# Current_Shunt_Amplifier.net
KiCad netlist of a schematic drawn in Altium Designer
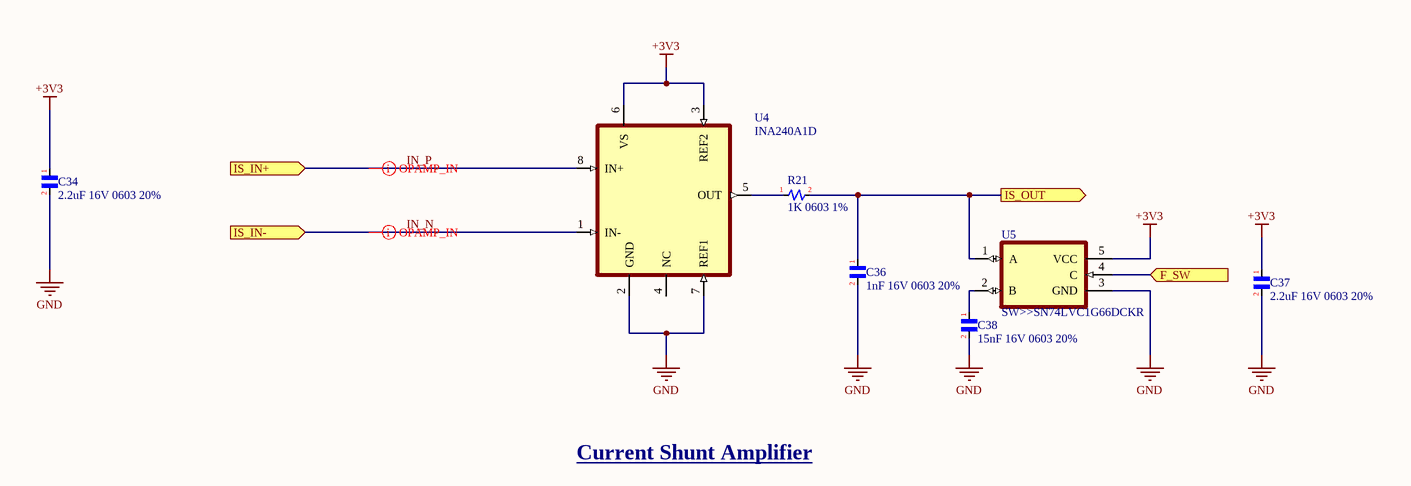
[diagram p0: Current_Shunt_Amplifier.SchDoc]

(export (version "E")
  (design (tool "Eeschema 10.0.6"))
  (components
    (comp (ref "C34")
      (value "2.2uF 16V 0603 20%")
      (footprint "C_0603")
      (description "CAP  0603 20%")
      (libsource (lib "Walton_EED") (part "Capacitor{gt}{gt} Non-Polar"))
    )
    (comp (ref "C36")
      (value "1nF 16V 0603 20%")
      (footprint "C_0603")
      (description "CAP  0603 20%")
      (libsource (lib "Walton_EED") (part "Capacitor{gt}{gt} Non-Polar"))
    )
    (comp (ref "C37")
      (value "2.2uF 16V 0603 20%")
      (footprint "C_0603")
      (description "CAP  0603 20%")
      (libsource (lib "Walton_EED") (part "Capacitor{gt}{gt} Non-Polar"))
    )
    (comp (ref "C38")
      (value "15nF 16V 0603 20%")
      (footprint "C_0603")
      (description "CAP  0603 20%")
      (libsource (lib "Walton_EED") (part "Capacitor{gt}{gt} Non-Polar"))
    )
    (comp (ref "R21")
      (value "1K 0603 1%")
      (footprint "R_0603")
      (description "RES 0603 20%")
      (libsource (lib "Walton_EED") (part "Resistor{gt}{gt} General Purpose"))
    )
    (comp (ref "U4")
      (value "INA240A1D")
      (footprint "SOIC127P599X175-8N")
      (description "-4 to 80V, bidirectional, ultra-precise current sense amplifier with enhanced PWM rejection")
      (fields (field (name "MF") "Texas Instruments"))
      (libsource (lib "Walton_EED_13_05_2024") (part "INA240A1D"))
    )
    (comp (ref "U5")
      (value "SW>>SN74LVC1G66DCKR")
      (footprint "SOT65P210X110-5N")
      (description "5-V, 1:1 (SPST), 1-channel analog switch")
      (fields (field (name "MF") "Texas Instruments") (field (name "MP") "SN74LVC1G66DCKR"))
      (libsource (lib "Walton_EED_13_05_2024") (part "SW{gt}{gt}SN74LVC1G66DCKR"))
    )
  )
  (nets
    (net (code "1") (name "+3V3") (class "Default")
      (node (ref "C34") (pin "1") (pinfunction "1_1") (pintype "passive"))
      (node (ref "C37") (pin "1") (pinfunction "1_1") (pintype "passive"))
      (node (ref "U4") (pin "3") (pinfunction "REF2_3") (pintype "input"))
      (node (ref "U4") (pin "6") (pinfunction "VS_6") (pintype "power_in"))
      (node (ref "U5") (pin "5") (pinfunction "VCC_5") (pintype "power_in"))
    )
    (net (code "2") (name "/F_SW") (class "Default")
      (node (ref "U5") (pin "4") (pinfunction "C_4") (pintype "input"))
    )
    (net (code "3") (name "/IN_N") (class "Default")
      (node (ref "U4") (pin "1") (pinfunction "IN-_1") (pintype "input"))
    )
    (net (code "4") (name "/IN_P") (class "Default")
      (node (ref "U4") (pin "8") (pinfunction "IN+_8") (pintype "input"))
    )
    (net (code "5") (name "/IS_OUT") (class "Default")
      (node (ref "C36") (pin "1") (pinfunction "1_1") (pintype "passive"))
      (node (ref "R21") (pin "2") (pinfunction "2_2") (pintype "passive"))
      (node (ref "U5") (pin "1") (pinfunction "A_1") (pintype "bidirectional"))
    )
    (net (code "6") (name "GND") (class "Default")
      (node (ref "C34") (pin "2") (pinfunction "2_2") (pintype "passive"))
      (node (ref "C36") (pin "2") (pinfunction "2_2") (pintype "passive"))
      (node (ref "C37") (pin "2") (pinfunction "2_2") (pintype "passive"))
      (node (ref "C38") (pin "2") (pinfunction "2_2") (pintype "passive"))
      (node (ref "U4") (pin "2") (pinfunction "GND_2") (pintype "power_in"))
      (node (ref "U4") (pin "7") (pinfunction "REF1_7") (pintype "input"))
      (node (ref "U5") (pin "3") (pinfunction "GND_3") (pintype "power_in"))
    )
    (net (code "7") (name "Net-(U4-OUT)") (class "Default")
      (node (ref "R21") (pin "1") (pinfunction "1_1") (pintype "passive"))
      (node (ref "U4") (pin "5") (pinfunction "OUT_5") (pintype "output"))
    )
    (net (code "8") (name "Net-(U5-B)") (class "Default")
      (node (ref "C38") (pin "1") (pinfunction "1_1") (pintype "passive"))
      (node (ref "U5") (pin "2") (pinfunction "B_2") (pintype "bidirectional"))
    )
    (net (code "9") (name "unconnected-(U4-NC-Pad4)") (class "Default")
      (node (ref "U4") (pin "4") (pinfunction "NC_4") (pintype "passive"))
    )
  )
)
